# design.net
KiCad netlist of a schematic drawn in Altium Designer
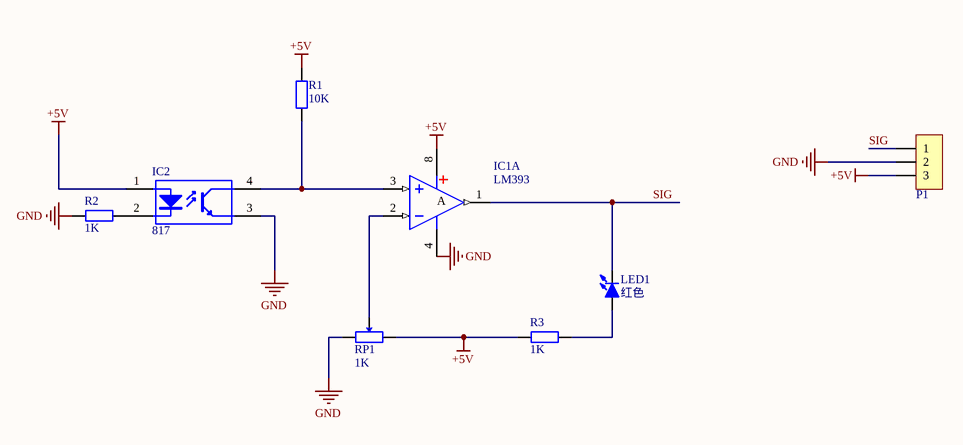
[diagram p0: 传感.SchDoc]

(export (version "E")
  (design (tool "Eeschema 10.0.6"))
  (components
    (comp (ref "IC1")
      (value "LM393")
      (footprint "DIP8-300")
      (description "双路电压比较")
      (fields (field (name "版权归属") "封装库来自淘宝 ID：黄晶宝石"))
      (libsource (lib "1.0 - 常见芯片") (part "LM393"))
    )
    (comp (ref "IC2")
      (value "817")
      (footprint "DIP4-300")
      (description "线性光耦")
      (fields (field (name "版权归属") "封装库来自淘宝 ID：黄晶宝石"))
      (libsource (lib "1.2 - 传感元件") (part "817"))
    )
    (comp (ref "LED1")
      (value "红色")
      (footprint "LED 0805R")
      (description "贴片LED")
      (fields (field (name "版权归属") "封装库来自淘宝 ID：黄晶宝石"))
      (libsource (lib "0.3 - LED发光二极管") (part "LED-SMD"))
    )
    (comp (ref "P1")
      (value "HDR-1X3")
      (footprint "KF301-5.0-3P")
      (description "3P接插件")
      (fields (field (name "版权归属") "封装库来自淘宝 ID：黄晶宝石"))
      (libsource (lib "6.0 - 接插件-脚距5.0") (part "Header 3"))
    )
    (comp (ref "R1")
      (value "10K")
      (footprint "R 0805_L")
      (description "贴片电阻")
      (fields (field (name "版权归属") "来自淘宝 ID：黄晶宝石"))
      (libsource (lib "0.1 - 电阻-电容-电感") (part "R"))
    )
    (comp (ref "R2")
      (value "1K")
      (footprint "R 0805_L")
      (description "贴片电阻")
      (fields (field (name "版权归属") "来自淘宝 ID：黄晶宝石"))
      (libsource (lib "0.1 - 电阻-电容-电感") (part "R"))
    )
    (comp (ref "R3")
      (value "1K")
      (footprint "R 0805_L")
      (description "贴片电阻")
      (fields (field (name "版权归属") "来自淘宝 ID：黄晶宝石"))
      (libsource (lib "0.1 - 电阻-电容-电感") (part "R"))
    )
    (comp (ref "RP1")
      (value "1K")
      (footprint "3296W")
      (description "单联电位器")
      (fields (field (name "版权归属") "封装库来自淘宝 ID：黄晶宝石"))
      (libsource (lib "0.1 - 电阻-电容-电感") (part "RP"))
    )
  )
  (nets
    (net (code "1") (name "+5V") (class "Default")
      (node (ref "IC1") (pin "8") (pinfunction "V+_8") (pintype "power_in"))
      (node (ref "IC2") (pin "1") (pinfunction "A_1") (pintype "passive"))
      (node (ref "P1") (pin "3") (pinfunction "3_3") (pintype "passive"))
      (node (ref "R1") (pin "2") (pinfunction "2_2") (pintype "passive"))
      (node (ref "R3") (pin "1") (pinfunction "1_1") (pintype "passive"))
      (node (ref "RP1") (pin "3") (pinfunction "3_3") (pintype "passive"))
    )
    (net (code "2") (name "/SIG") (class "Default")
      (node (ref "IC1") (pin "1") (pinfunction "OUT_1") (pintype "output"))
      (node (ref "LED1") (pin "2") (pinfunction "K_2") (pintype "passive"))
      (node (ref "P1") (pin "1") (pinfunction "1_1") (pintype "passive"))
    )
    (net (code "3") (name "GND") (class "Default")
      (node (ref "IC1") (pin "4") (pinfunction "V-_4") (pintype "power_in"))
      (node (ref "IC2") (pin "3") (pinfunction "E_3") (pintype "passive"))
      (node (ref "P1") (pin "2") (pinfunction "2_2") (pintype "passive"))
      (node (ref "R2") (pin "1") (pinfunction "1_1") (pintype "passive"))
      (node (ref "RP1") (pin "1") (pinfunction "1_1") (pintype "passive"))
    )
    (net (code "4") (name "Net-(IC1A-IN+)") (class "Default")
      (node (ref "IC1") (pin "3") (pinfunction "IN+_3") (pintype "input"))
      (node (ref "IC2") (pin "4") (pinfunction "C_4") (pintype "passive"))
      (node (ref "R1") (pin "1") (pinfunction "1_1") (pintype "passive"))
    )
    (net (code "5") (name "Net-(IC1A-IN-)") (class "Default")
      (node (ref "IC1") (pin "2") (pinfunction "IN-_2") (pintype "input"))
      (node (ref "RP1") (pin "2") (pinfunction "2_2") (pintype "passive"))
    )
    (net (code "6") (name "Net-(IC2-K)") (class "Default")
      (node (ref "IC2") (pin "2") (pinfunction "K_2") (pintype "passive"))
      (node (ref "R2") (pin "2") (pinfunction "2_2") (pintype "passive"))
    )
    (net (code "7") (name "Net-(LED1-A)") (class "Default")
      (node (ref "LED1") (pin "1") (pinfunction "A_1") (pintype "passive"))
      (node (ref "R3") (pin "2") (pinfunction "2_2") (pintype "passive"))
    )
  )
)
